# LED.net
KiCad netlist of a schematic drawn in EAGLE
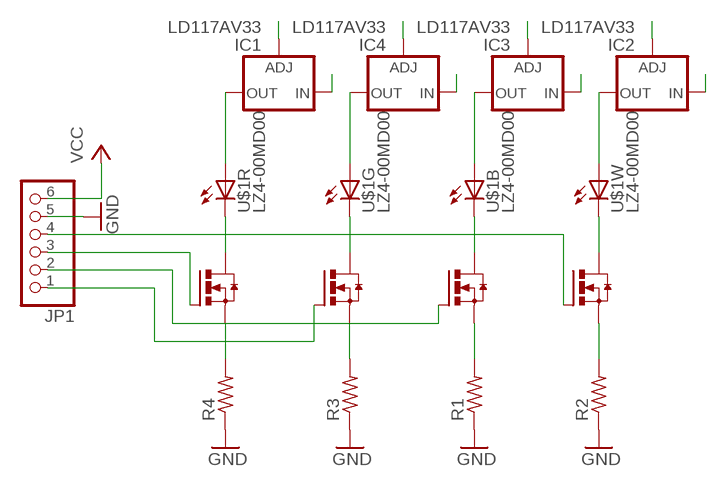
[diagram p0: schematic, sheet 1]

(export (version "E")
  (design (tool "Eeschema 10.0.6"))
  (components
    (comp (ref "IC1")
      (value "LD117AV33")
      (footprint "eagle-import:TO220L1")
      (libsource (lib "eagle-import") (part "LD117A?V33"))
    )
    (comp (ref "IC2")
      (value "LD117AV33")
      (footprint "eagle-import:TO220L1")
      (libsource (lib "eagle-import") (part "LD117A?V33"))
    )
    (comp (ref "IC3")
      (value "LD117AV33")
      (footprint "eagle-import:TO220L1")
      (libsource (lib "eagle-import") (part "LD117A?V33"))
    )
    (comp (ref "IC4")
      (value "LD117AV33")
      (footprint "eagle-import:TO220L1")
      (libsource (lib "eagle-import") (part "LD117A?V33"))
    )
    (comp (ref "JP1")
      (value "PINHD-1X6")
      (footprint "eagle-import:1X06")
      (libsource (lib "eagle-import") (part "PINHD-1X6"))
    )
    (comp (ref "Q1")
      (value "N-HEXFET_SOT323-")
      (footprint "eagle-import:SOT223")
      (libsource (lib "eagle-import") (part "N-HEXFET_?-SOT323"))
    )
    (comp (ref "Q2")
      (value "N-HEXFET_SOT323-")
      (footprint "eagle-import:SOT223")
      (libsource (lib "eagle-import") (part "N-HEXFET_?-SOT323"))
    )
    (comp (ref "Q3")
      (value "N-HEXFET_SOT323-")
      (footprint "eagle-import:SOT223")
      (libsource (lib "eagle-import") (part "N-HEXFET_?-SOT323"))
    )
    (comp (ref "Q4")
      (value "N-HEXFET_SOT323-")
      (footprint "eagle-import:SOT223")
      (libsource (lib "eagle-import") (part "N-HEXFET_?-SOT323"))
    )
    (comp (ref "R1")
      (value "R-US_0204/7")
      (footprint "eagle-import:0204_7")
      (libsource (lib "eagle-import") (part "R-US_0204/7"))
    )
    (comp (ref "R2")
      (value "R-US_0204/7")
      (footprint "eagle-import:0204_7")
      (libsource (lib "eagle-import") (part "R-US_0204/7"))
    )
    (comp (ref "R3")
      (value "R-US_0204/7")
      (footprint "eagle-import:0204_7")
      (libsource (lib "eagle-import") (part "R-US_0204/7"))
    )
    (comp (ref "R4")
      (value "R-US_0204/7")
      (footprint "eagle-import:0204_7")
      (libsource (lib "eagle-import") (part "R-US_0204/7"))
    )
    (comp (ref "U$1")
      (value "LZ4-00MD00")
      (footprint "eagle-import:LZ4-00MD0")
      (libsource (lib "eagle-import") (part "LZ4-00MD00"))
    )
  )
  (nets
    (net (code "1") (name "GND") (class "Default")
      (node (ref "IC1") (pin "1") (pinfunction "ADJ_1") (pintype "input"))
      (node (ref "IC2") (pin "1") (pinfunction "ADJ_1") (pintype "input"))
      (node (ref "IC3") (pin "1") (pinfunction "ADJ_1") (pintype "input"))
      (node (ref "IC4") (pin "1") (pinfunction "ADJ_1") (pintype "input"))
      (node (ref "JP1") (pin "5") (pinfunction "5_5") (pintype "passive"))
      (node (ref "R1") (pin "1") (pinfunction "1_1") (pintype "passive"))
      (node (ref "R2") (pin "1") (pinfunction "1_1") (pintype "passive"))
      (node (ref "R3") (pin "1") (pinfunction "1_1") (pintype "passive"))
      (node (ref "R4") (pin "1") (pinfunction "1_1") (pintype "passive"))
    )
    (net (code "2") (name "Net-(IC1-OUT)") (class "Default")
      (node (ref "IC1") (pin "2") (pinfunction "OUT_2") (pintype "passive"))
      (node (ref "U$1") (pin "3") (pinfunction "A_3") (pintype "passive"))
    )
    (net (code "3") (name "Net-(IC2-OUT)") (class "Default")
      (node (ref "IC2") (pin "2") (pinfunction "OUT_2") (pintype "passive"))
      (node (ref "U$1") (pin "1") (pinfunction "A_1") (pintype "passive"))
    )
    (net (code "4") (name "Net-(IC3-OUT)") (class "Default")
      (node (ref "IC3") (pin "2") (pinfunction "OUT_2") (pintype "passive"))
      (node (ref "U$1") (pin "7") (pinfunction "A_7") (pintype "passive"))
    )
    (net (code "5") (name "Net-(IC4-OUT)") (class "Default")
      (node (ref "IC4") (pin "2") (pinfunction "OUT_2") (pintype "passive"))
      (node (ref "U$1") (pin "5") (pinfunction "A_5") (pintype "passive"))
    )
    (net (code "6") (name "Net-(Q1-D)") (class "Default")
      (node (ref "Q1") (pin "4") (pinfunction "D_4") (pintype "passive"))
      (node (ref "U$1") (pin "8") (pinfunction "C_8") (pintype "passive"))
    )
    (net (code "7") (name "Net-(Q1-G)") (class "Default")
      (node (ref "JP1") (pin "2") (pinfunction "2_2") (pintype "passive"))
      (node (ref "Q1") (pin "1") (pinfunction "G_1") (pintype "passive"))
    )
    (net (code "8") (name "Net-(Q1-S)") (class "Default")
      (node (ref "Q1") (pin "3") (pinfunction "S_3") (pintype "passive"))
      (node (ref "R1") (pin "2") (pinfunction "2_2") (pintype "passive"))
    )
    (net (code "9") (name "Net-(Q2-D)") (class "Default")
      (node (ref "Q2") (pin "4") (pinfunction "D_4") (pintype "passive"))
      (node (ref "U$1") (pin "6") (pinfunction "C_6") (pintype "passive"))
    )
    (net (code "10") (name "Net-(Q2-G)") (class "Default")
      (node (ref "JP1") (pin "1") (pinfunction "1_1") (pintype "passive"))
      (node (ref "Q2") (pin "1") (pinfunction "G_1") (pintype "passive"))
    )
    (net (code "11") (name "Net-(Q2-S)") (class "Default")
      (node (ref "Q2") (pin "3") (pinfunction "S_3") (pintype "passive"))
      (node (ref "R3") (pin "2") (pinfunction "2_2") (pintype "passive"))
    )
    (net (code "12") (name "Net-(Q3-D)") (class "Default")
      (node (ref "Q3") (pin "4") (pinfunction "D_4") (pintype "passive"))
      (node (ref "U$1") (pin "4") (pinfunction "C_4") (pintype "passive"))
    )
    (net (code "13") (name "Net-(Q3-G)") (class "Default")
      (node (ref "JP1") (pin "3") (pinfunction "3_3") (pintype "passive"))
      (node (ref "Q3") (pin "1") (pinfunction "G_1") (pintype "passive"))
    )
    (net (code "14") (name "Net-(Q3-S)") (class "Default")
      (node (ref "Q3") (pin "3") (pinfunction "S_3") (pintype "passive"))
      (node (ref "R4") (pin "2") (pinfunction "2_2") (pintype "passive"))
    )
    (net (code "15") (name "Net-(Q4-D)") (class "Default")
      (node (ref "Q4") (pin "4") (pinfunction "D_4") (pintype "passive"))
      (node (ref "U$1") (pin "2") (pinfunction "C_2") (pintype "passive"))
    )
    (net (code "16") (name "Net-(Q4-G)") (class "Default")
      (node (ref "JP1") (pin "4") (pinfunction "4_4") (pintype "passive"))
      (node (ref "Q4") (pin "1") (pinfunction "G_1") (pintype "passive"))
    )
    (net (code "17") (name "Net-(Q4-S)") (class "Default")
      (node (ref "Q4") (pin "3") (pinfunction "S_3") (pintype "passive"))
      (node (ref "R2") (pin "2") (pinfunction "2_2") (pintype "passive"))
    )
    (net (code "18") (name "VCC") (class "Default")
      (node (ref "IC1") (pin "3") (pinfunction "IN_3") (pintype "input"))
      (node (ref "IC2") (pin "3") (pinfunction "IN_3") (pintype "input"))
      (node (ref "IC3") (pin "3") (pinfunction "IN_3") (pintype "input"))
      (node (ref "IC4") (pin "3") (pinfunction "IN_3") (pintype "input"))
      (node (ref "JP1") (pin "6") (pinfunction "6_6") (pintype "passive"))
    )
  )
)
